# Agrobot_1_2.net
KiCad netlist of a schematic drawn in Altium Designer
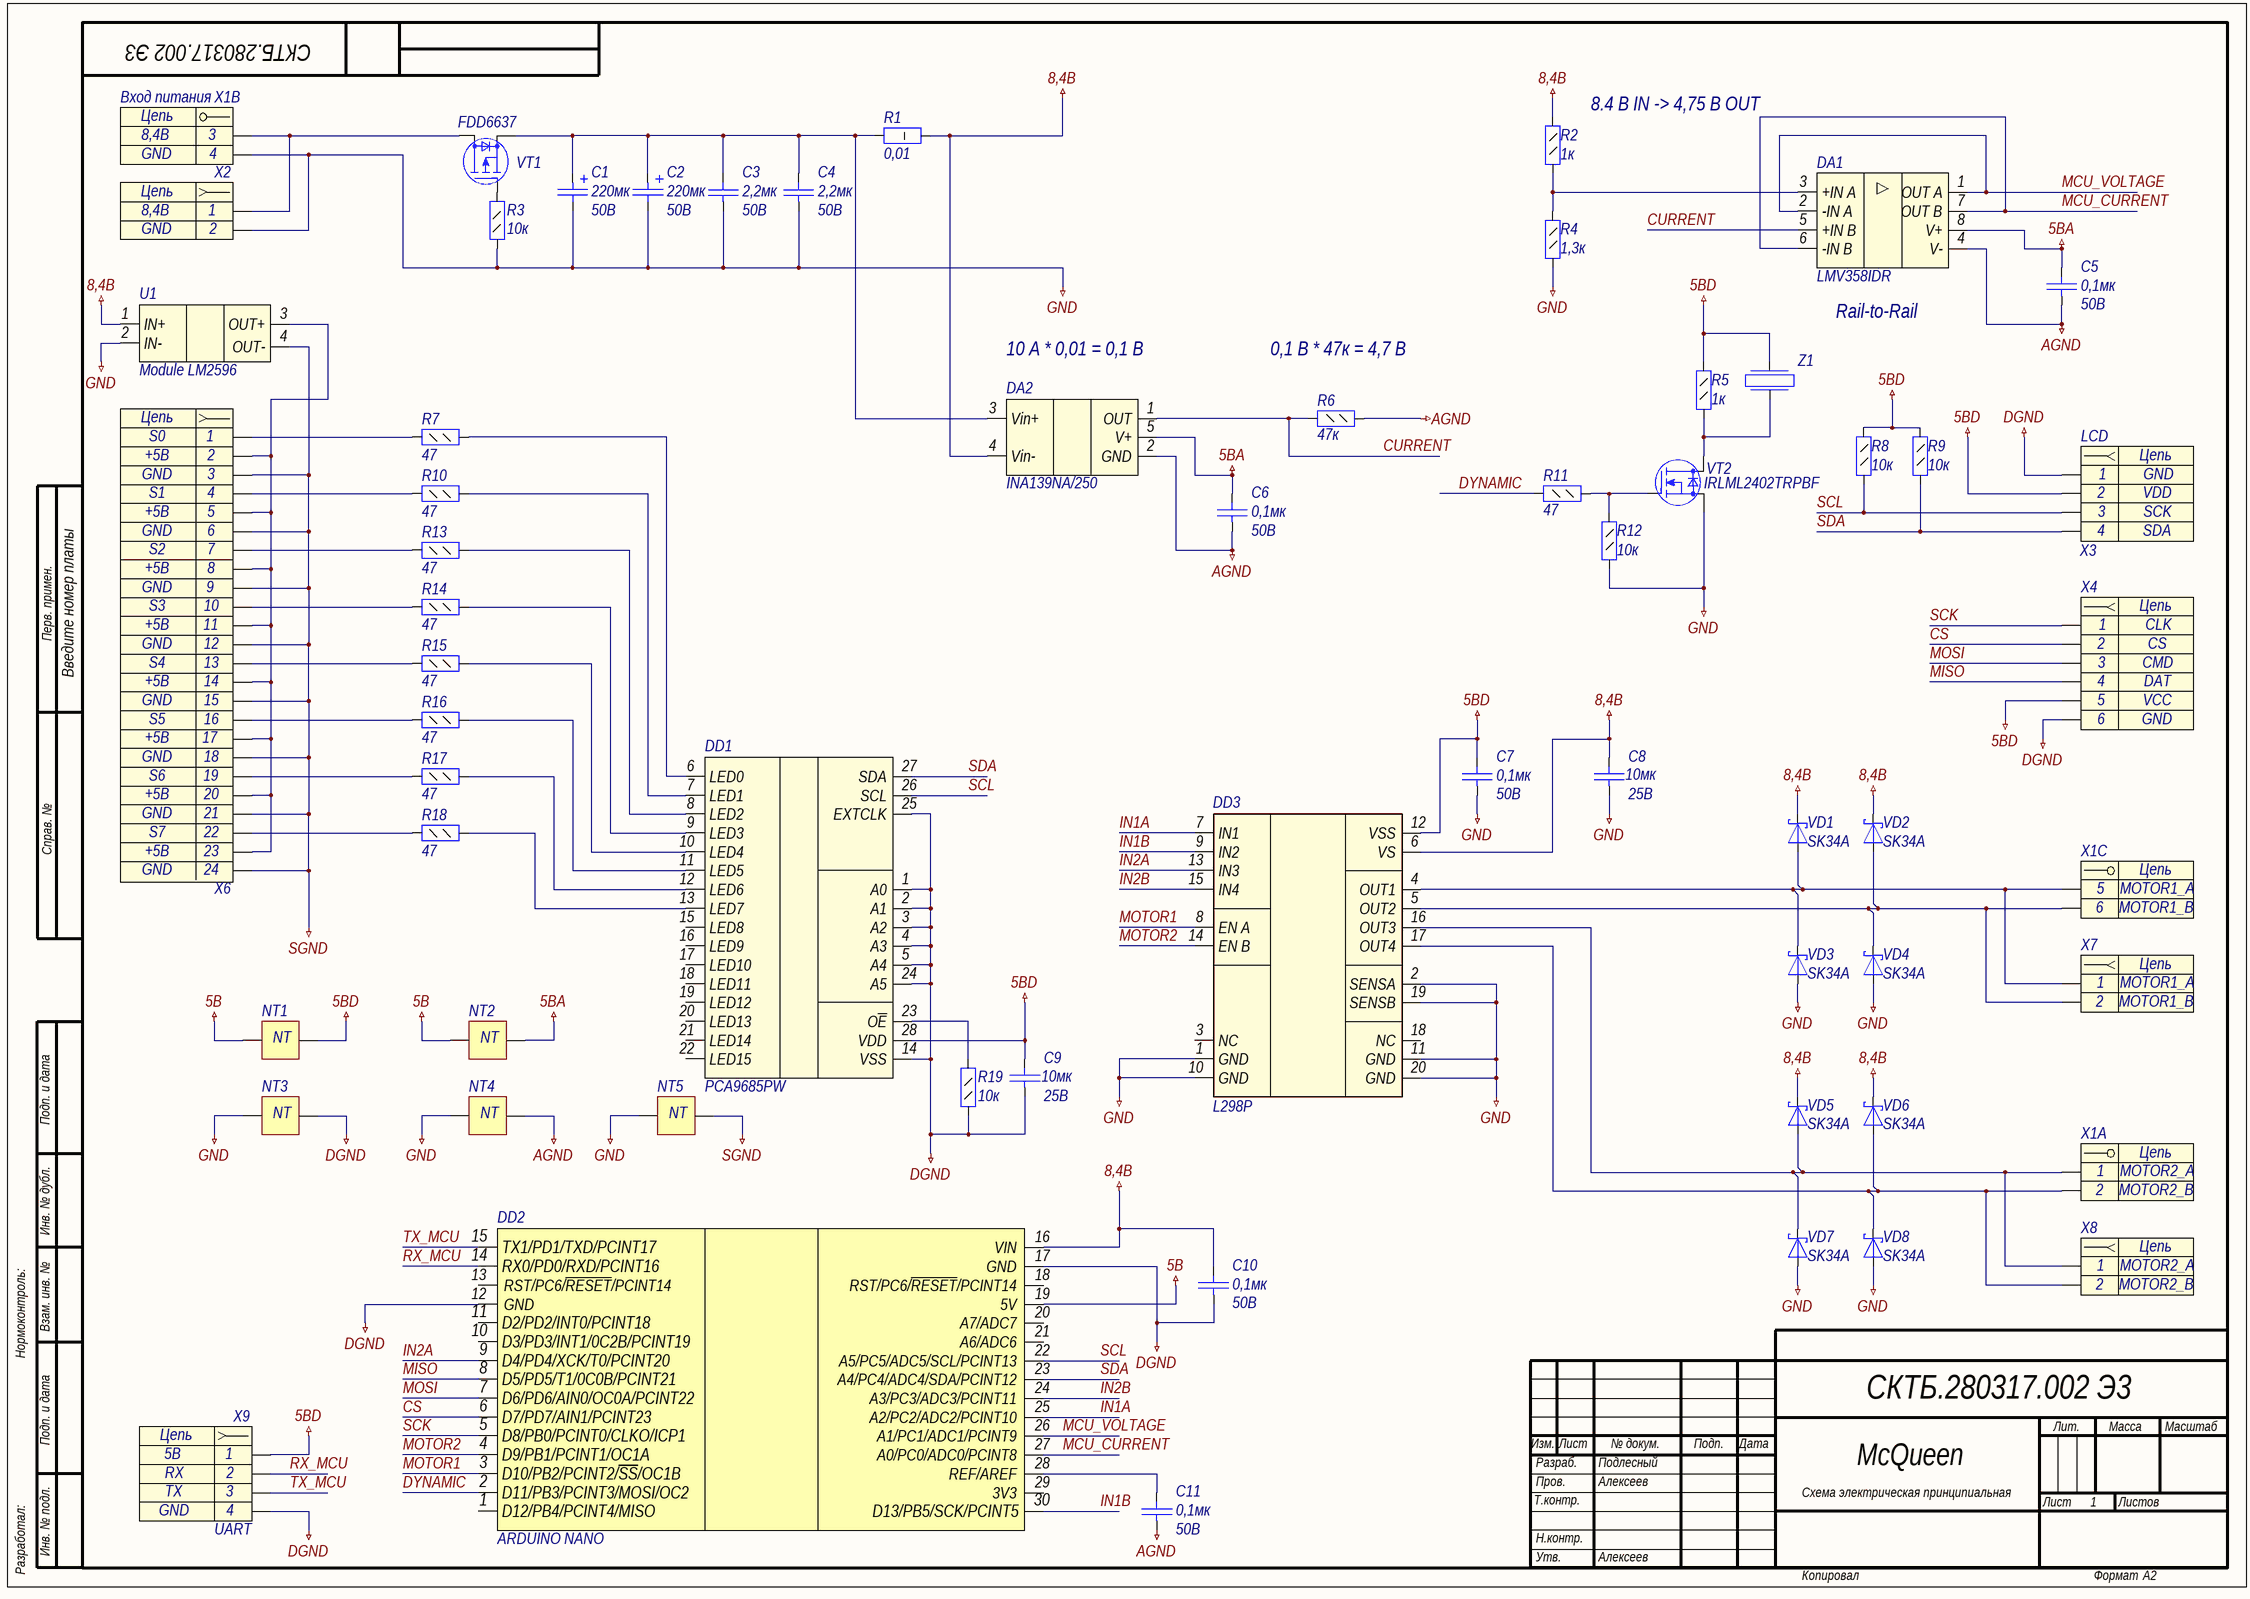
[diagram p0: Agrobot_1.2.SchDoc]

(export (version "E")
  (design (tool "Eeschema 10.0.6"))
  (components
    (comp (ref "C1")
      (value "220мк")
      (footprint "Cap_SMD_radial_polar(10x10.5)")
      (description "Конденсатор полярный")
      (fields
        (field (name "VOLTAGE") "50В")
        (field (name "PART NUMBER") "ECAP SMD")
        (field (name "Comment") "Capacitor_pol")
      )
      (libsource (lib "MOP44") (part "Capacitor_pol"))
    )
    (comp (ref "C2")
      (value "220мк")
      (footprint "Cap_SMD_radial_polar(10x10.5)")
      (description "Конденсатор полярный")
      (fields
        (field (name "VOLTAGE") "50В")
        (field (name "PART NUMBER") "ECAP SMD")
        (field (name "Comment") "Capacitor_pol")
      )
      (libsource (lib "MOP44") (part "Capacitor_pol"))
    )
    (comp (ref "C3")
      (value "2,2мк")
      (footprint "C1206")
      (description "Конденсатор")
      (fields
        (field (name "VOLTAGE") "50В")
        (field (name "PART NUMBER") "GRM31CR71H225KA88**L")
        (field (name "Comment") "Capacitor")
      )
      (libsource (lib "MOP44") (part "Capacitor"))
    )
    (comp (ref "C4")
      (value "2,2мк")
      (footprint "C1206")
      (description "Конденсатор")
      (fields
        (field (name "VOLTAGE") "50В")
        (field (name "PART NUMBER") "GRM31CR71H225KA88**L")
        (field (name "Comment") "Capacitor")
      )
      (libsource (lib "MOP44") (part "Capacitor"))
    )
    (comp (ref "C5")
      (value "0,1мк")
      (footprint "C0805")
      (description "Конденсатор")
      (fields
        (field (name "VOLTAGE") "50B")
        (field (name "PART NUMBER") "GRM21BR71E225K")
        (field (name "Comment") "Capacitor")
      )
      (libsource (lib "MOP44") (part "Capacitor"))
    )
    (comp (ref "C6")
      (value "0,1мк")
      (footprint "C0805")
      (description "Конденсатор")
      (fields
        (field (name "VOLTAGE") "50B")
        (field (name "PART NUMBER") "GRM21BR71E225K")
        (field (name "Comment") "Capacitor")
      )
      (libsource (lib "MOP44") (part "Capacitor"))
    )
    (comp (ref "C7")
      (value "0,1мк")
      (footprint "C0805")
      (description "Конденсатор")
      (fields
        (field (name "VOLTAGE") "50B")
        (field (name "PART NUMBER") "GRM21BR71E225K")
        (field (name "Comment") "Capacitor")
      )
      (libsource (lib "MOP44") (part "Capacitor"))
    )
    (comp (ref "C8")
      (value "10мк")
      (footprint "C1210")
      (description "Конденсатор")
      (fields
        (field (name "VOLTAGE") "25В")
        (field (name "PART NUMBER") "GRM32ER61A106K")
        (field (name "Comment") "Capacitor")
      )
      (libsource (lib "MOP44") (part "Capacitor"))
    )
    (comp (ref "C9")
      (value "10мк")
      (footprint "C1210")
      (description "Конденсатор")
      (fields
        (field (name "VOLTAGE") "25В")
        (field (name "PART NUMBER") "GRM32ER61A106K")
        (field (name "Comment") "Capacitor")
      )
      (libsource (lib "MOP44") (part "Capacitor"))
    )
    (comp (ref "C10")
      (value "0,1мк")
      (footprint "C0805")
      (description "Конденсатор")
      (fields
        (field (name "VOLTAGE") "50B")
        (field (name "PART NUMBER") "GRM21BR71E225K")
        (field (name "Comment") "Capacitor")
      )
      (libsource (lib "MOP44") (part "Capacitor"))
    )
    (comp (ref "C11")
      (value "0,1мк")
      (footprint "C0805")
      (description "Конденсатор")
      (fields
        (field (name "VOLTAGE") "50B")
        (field (name "PART NUMBER") "GRM21BR71E225K")
        (field (name "Comment") "Capacitor")
      )
      (libsource (lib "MOP44") (part "Capacitor"))
    )
    (comp (ref "DA1")
      (value "LMV358IDR")
      (footprint "SO8")
      (description "LOW-VOLTAGE RAIL-TO-RAIL OUTPUT OPERATIONAL AMPLIFIERS")
      (libsource (lib "MOP44") (part "LMV358IDR"))
    )
    (comp (ref "DA2")
      (value "INA139NA/250")
      (footprint "SOT23-5")
      (description "Измерительный датчик тока")
      (libsource (lib "MOP44") (part "INA139NA/250"))
    )
    (comp (ref "DD1")
      (value "PCA9685PW")
      (footprint "TSSOP28")
      (description "Драйвер светодиода, 16 выходов")
      (libsource (lib "MOP44") (part "PCA9685PW"))
    )
    (comp (ref "DD2")
      (value "ARDUINO NANO")
      (footprint "ARDUINO NANO")
      (description "Отладочная плата ATmega328")
      (libsource (lib "MOP44") (part "ARDUINO NANO"))
    )
    (comp (ref "DD3")
      (value "L298P")
      (footprint "POWERSO20")
      (description "FULL BRIDGE DC MOTOR DRIVER")
      (libsource (lib "MOP44") (part "L298P"))
    )
    (comp (ref "NT1")
      (value "Pofigistor")
      (footprint "Pofigistor0603")
      (libsource (lib "MOP44") (part "Pofigistor"))
    )
    (comp (ref "NT2")
      (value "Pofigistor")
      (footprint "Pofigistor0603")
      (libsource (lib "MOP44") (part "Pofigistor"))
    )
    (comp (ref "NT3")
      (value "Pofigistor")
      (footprint "Pofigistor0603")
      (libsource (lib "MOP44") (part "Pofigistor"))
    )
    (comp (ref "NT4")
      (value "Pofigistor")
      (footprint "Pofigistor0603")
      (libsource (lib "MOP44") (part "Pofigistor"))
    )
    (comp (ref "NT5")
      (value "Pofigistor")
      (footprint "Pofigistor0603")
      (libsource (lib "MOP44") (part "Pofigistor"))
    )
    (comp (ref "R1")
      (value "0,01")
      (footprint "R2512")
      (description "Резистор")
      (fields (field (name "POWER") "1Вт") (field (name "Comment") "Resistor_1Вт"))
      (libsource (lib "MOP44") (part "Resistor_1Вт"))
    )
    (comp (ref "R2")
      (value "1к")
      (footprint "R0805")
      (description "Резистор")
      (fields (field (name "POWER") "0,125Вт") (field (name "Comment") "Resistor_0,125Вт"))
      (libsource (lib "") (part "Resistor_0,125Вт_1"))
    )
    (comp (ref "R3")
      (value "10к")
      (footprint "R0805")
      (description "Резистор")
      (fields (field (name "PART NUMBER") "RC0805FR-0710KL") (field (name "POWER") "0,125Вт"))
      (libsource (lib "") (part "Resistor_0,125Вт_3"))
    )
    (comp (ref "R4")
      (value "1,3к")
      (footprint "R0805")
      (description "Резистор")
      (fields (field (name "POWER") "0,125Вт") (field (name "Comment") "Resistor_0,125Вт"))
      (libsource (lib "") (part "Resistor_0,125Вт_1"))
    )
    (comp (ref "R5")
      (value "1к")
      (footprint "R0805")
      (description "Резистор")
      (fields (field (name "POWER") "0,125Вт") (field (name "Comment") "Resistor_0,125Вт"))
      (libsource (lib "") (part "Resistor_0,125Вт_1"))
    )
    (comp (ref "R6")
      (value "47к")
      (footprint "R0805")
      (description "Резистор")
      (fields (field (name "POWER") "0,125Вт") (field (name "Comment") "Resistor_0,125Вт"))
      (libsource (lib "MOP44") (part "Resistor_0,125Вт"))
    )
    (comp (ref "R7")
      (value "47")
      (footprint "R0805")
      (description "Резистор")
      (fields (field (name "PART NUMBER") "RC0805FR-0747RL") (field (name "POWER") "0,125Вт"))
      (libsource (lib "") (part "Resistor_0,125Вт_2"))
    )
    (comp (ref "R8")
      (value "10к")
      (footprint "R0805")
      (description "Резистор")
      (fields (field (name "POWER") "0,125Вт") (field (name "Comment") "Resistor_0,125Вт"))
      (libsource (lib "") (part "Resistor_0,125Вт_1"))
    )
    (comp (ref "R9")
      (value "10к")
      (footprint "R0805")
      (description "Резистор")
      (fields (field (name "POWER") "0,125Вт") (field (name "Comment") "Resistor_0,125Вт"))
      (libsource (lib "") (part "Resistor_0,125Вт_1"))
    )
    (comp (ref "R10")
      (value "47")
      (footprint "R0805")
      (description "Резистор")
      (fields (field (name "PART NUMBER") "RC0805FR-0747RL") (field (name "POWER") "0,125Вт"))
      (libsource (lib "") (part "Resistor_0,125Вт_2"))
    )
    (comp (ref "R11")
      (value "47")
      (footprint "R0805")
      (description "Резистор")
      (fields (field (name "POWER") "0,125Вт") (field (name "Comment") "Resistor_0,125Вт"))
      (libsource (lib "MOP44") (part "Resistor_0,125Вт"))
    )
    (comp (ref "R12")
      (value "10к")
      (footprint "R0805")
      (description "Резистор")
      (fields (field (name "POWER") "0,125Вт") (field (name "Comment") "Resistor_0,125Вт"))
      (libsource (lib "") (part "Resistor_0,125Вт_1"))
    )
    (comp (ref "R13")
      (value "47")
      (footprint "R0805")
      (description "Резистор")
      (fields (field (name "PART NUMBER") "RC0805FR-0747RL") (field (name "POWER") "0,125Вт"))
      (libsource (lib "") (part "Resistor_0,125Вт_2"))
    )
    (comp (ref "R14")
      (value "47")
      (footprint "R0805")
      (description "Резистор")
      (fields (field (name "PART NUMBER") "RC0805FR-0747RL") (field (name "POWER") "0,125Вт"))
      (libsource (lib "") (part "Resistor_0,125Вт_2"))
    )
    (comp (ref "R15")
      (value "47")
      (footprint "R0805")
      (description "Резистор")
      (fields (field (name "PART NUMBER") "RC0805FR-0747RL") (field (name "POWER") "0,125Вт"))
      (libsource (lib "") (part "Resistor_0,125Вт_2"))
    )
    (comp (ref "R16")
      (value "47")
      (footprint "R0805")
      (description "Резистор")
      (fields (field (name "PART NUMBER") "RC0805FR-0747RL") (field (name "POWER") "0,125Вт"))
      (libsource (lib "") (part "Resistor_0,125Вт_2"))
    )
    (comp (ref "R17")
      (value "47")
      (footprint "R0805")
      (description "Резистор")
      (fields (field (name "PART NUMBER") "RC0805FR-0747RL") (field (name "POWER") "0,125Вт"))
      (libsource (lib "") (part "Resistor_0,125Вт_2"))
    )
    (comp (ref "R18")
      (value "47")
      (footprint "R0805")
      (description "Резистор")
      (fields (field (name "PART NUMBER") "RC0805FR-0747RL") (field (name "POWER") "0,125Вт"))
      (libsource (lib "") (part "Resistor_0,125Вт_2"))
    )
    (comp (ref "R19")
      (value "10к")
      (footprint "R0805")
      (description "Резистор")
      (fields (field (name "POWER") "0,125Вт") (field (name "Comment") "Resistor_0,125Вт"))
      (libsource (lib "") (part "Resistor_0,125Вт_3"))
    )
    (comp (ref "U1")
      (value "Module LM2596")
      (footprint "module LM2596")
      (description "Low-Dropout Regulator for 5-V to 3.3-V Conversion")
      (libsource (lib "MOP44") (part "Module LM2596"))
    )
    (comp (ref "VD1")
      (value "DiodeSchottky")
      (footprint "SMA")
      (description "Диод Шоттки")
      (fields (field (name "PART NUMBER") "SK34A"))
      (libsource (lib "MOP44") (part "DiodeSchottky"))
    )
    (comp (ref "VD2")
      (value "DiodeSchottky")
      (footprint "SMA")
      (description "Диод Шоттки")
      (fields (field (name "PART NUMBER") "SK34A"))
      (libsource (lib "MOP44") (part "DiodeSchottky"))
    )
    (comp (ref "VD3")
      (value "DiodeSchottky")
      (footprint "SMA")
      (description "Диод Шоттки")
      (fields (field (name "PART NUMBER") "SK34A"))
      (libsource (lib "MOP44") (part "DiodeSchottky"))
    )
    (comp (ref "VD4")
      (value "DiodeSchottky")
      (footprint "SMA")
      (description "Диод Шоттки")
      (fields (field (name "PART NUMBER") "SK34A"))
      (libsource (lib "MOP44") (part "DiodeSchottky"))
    )
    (comp (ref "VD5")
      (value "DiodeSchottky")
      (footprint "SMA")
      (description "Диод Шоттки")
      (fields (field (name "PART NUMBER") "SK34A"))
      (libsource (lib "MOP44") (part "DiodeSchottky"))
    )
    (comp (ref "VD6")
      (value "DiodeSchottky")
      (footprint "SMA")
      (description "Диод Шоттки")
      (fields (field (name "PART NUMBER") "SK34A"))
      (libsource (lib "MOP44") (part "DiodeSchottky"))
    )
    (comp (ref "VD7")
      (value "DiodeSchottky")
      (footprint "SMA")
      (description "Диод Шоттки")
      (fields (field (name "PART NUMBER") "SK34A"))
      (libsource (lib "MOP44") (part "DiodeSchottky"))
    )
    (comp (ref "VD8")
      (value "DiodeSchottky")
      (footprint "SMA")
      (description "Диод Шоттки")
      (fields (field (name "PART NUMBER") "SK34A"))
      (libsource (lib "MOP44") (part "DiodeSchottky"))
    )
    (comp (ref "VT1")
      (value "P-MOSFET")
      (footprint "D2PAK")
      (description "N-MOSFET")
      (fields (field (name "PART NUMBER") "FDD6637") (field (name "MANUFACTURER") "Fairchild Semiconductor"))
      (libsource (lib "MOP44") (part "P-MOSFET"))
    )
    (comp (ref "VT2")
      (value "N-MOSFET")
      (footprint "SOT23-3")
      (fields (field (name "PART NUMBER") "IRLML2402TRPBF"))
      (libsource (lib "MOP44") (part "N-MOSFET"))
    )
    (comp (ref "X1")
      (value "Вход питания")
      (footprint "TERMINAL-6WAY-5MM")
      (description "POWER")
      (libsource (lib "MOP44") (part "Header_6_motor"))
    )
    (comp (ref "X2")
      (value "Header_2_sct")
      (footprint "2HOLE_2.5")
      (description "Разъем - 2 конт. розетка")
      (libsource (lib "MOP44") (part "Header_2_sct"))
    )
    (comp (ref "X3")
      (value "LCD")
      (footprint "PLS-4HOLES")
      (description "Разъем - 4 конт. розетка")
      (libsource (lib "MOP44") (part "Header_4_sct"))
    )
    (comp (ref "X4")
      (value "Header_6_sct")
      (footprint "PSP_ANTENNA")
      (description "Разъем - 6 конт. розетка")
      (libsource (lib "MOP44") (part "Header_6_sct"))
    )
    (comp (ref "X6")
      (value "Header_24_sct")
      (footprint "PLS-24-3")
      (description "Разъем - 5 конт. розетка")
      (libsource (lib "MOP44") (part "Header_24_sct"))
    )
    (comp (ref "X7")
      (value "Header_2_sct")
      (footprint "2HOLE_2.5")
      (description "Разъем - 2 конт. розетка")
      (libsource (lib "") (part "Header_2_sct_1"))
    )
    (comp (ref "X8")
      (value "Header_2_sct")
      (footprint "2HOLE_2.5")
      (description "Разъем - 2 конт. розетка")
      (libsource (lib "") (part "Header_2_sct_1"))
    )
    (comp (ref "X9")
      (value "UART")
      (footprint "PLS-4HOLES")
      (description "Разъем - 4 конт. розетка")
      (libsource (lib "") (part "Header_4_sct_1"))
    )
    (comp (ref "Z1")
      (value "~")
      (footprint "Buzzer_9mm")
      (description "Пьезоизлучатель звуковой без генератора")
      (fields (field (name "PART NUMBER") "HC0905F"))
      (libsource (lib "MOP44") (part "Buzzer"))
    )
  )
  (nets
    (net (code "1") (name "/CS") (class "Default")
      (node (ref "DD2") (pin "6") (pinfunction "D7/PD7/AIN1/PCINT23_6") (pintype "passive"))
      (node (ref "X4") (pin "2") (pinfunction "2_2") (pintype "passive"))
    )
    (net (code "2") (name "/CURRENT") (class "Default")
      (node (ref "DA1") (pin "5") (pinfunction "+IN_B_5") (pintype "passive"))
      (node (ref "DA2") (pin "1") (pinfunction "OUT_1") (pintype "power_in"))
      (node (ref "R6") (pin "2") (pinfunction "2_2") (pintype "passive"))
    )
    (net (code "3") (name "/DYNAMIC") (class "Default")
      (node (ref "DD2") (pin "2") (pinfunction "D11/PB3/PCINT3/MOSI/OC2_2") (pintype "passive"))
      (node (ref "R11") (pin "2") (pinfunction "2_2") (pintype "passive"))
    )
    (net (code "4") (name "/IN1A") (class "Default")
      (node (ref "DD2") (pin "25") (pinfunction "A2/PC2/ADC2/PCINT10_25") (pintype "passive"))
      (node (ref "DD3") (pin "7") (pinfunction "IN1_7") (pintype "passive"))
    )
    (net (code "5") (name "/IN1B") (class "Default")
      (node (ref "DD2") (pin "30") (pinfunction "D13/PB5/SCK/PCINT5_30") (pintype "passive"))
      (node (ref "DD3") (pin "9") (pinfunction "IN2_9") (pintype "passive"))
    )
    (net (code "6") (name "/IN2A") (class "Default")
      (node (ref "DD2") (pin "9") (pinfunction "D4/PD4/XCK/T0/PCINT20_9") (pintype "passive"))
      (node (ref "DD3") (pin "13") (pinfunction "IN3_13") (pintype "passive"))
    )
    (net (code "7") (name "/IN2B") (class "Default")
      (node (ref "DD2") (pin "24") (pinfunction "A3/PC3/ADC3/PCINT11_24") (pintype "passive"))
      (node (ref "DD3") (pin "15") (pinfunction "IN4_15") (pintype "passive"))
    )
    (net (code "8") (name "/MCU_CURRENT") (class "Default")
      (node (ref "DA1") (pin "6") (pinfunction "-IN_B_6") (pintype "passive"))
      (node (ref "DA1") (pin "7") (pinfunction "OUT_B_7") (pintype "passive"))
      (node (ref "DD2") (pin "27") (pinfunction "A0/PC0/ADC0/PCINT8_27") (pintype "passive"))
    )
    (net (code "9") (name "/MCU_VOLTAGE") (class "Default")
      (node (ref "DA1") (pin "1") (pinfunction "OUT_A_1") (pintype "passive"))
      (node (ref "DA1") (pin "2") (pinfunction "-IN_A_2") (pintype "passive"))
      (node (ref "DD2") (pin "26") (pinfunction "A1/PC1/ADC1/PCINT9_26") (pintype "passive"))
    )
    (net (code "10") (name "/MISO") (class "Default")
      (node (ref "DD2") (pin "8") (pinfunction "D5/PD5/T1/0C0B/PCINT21_8") (pintype "passive"))
      (node (ref "X4") (pin "4") (pinfunction "4_4") (pintype "passive"))
    )
    (net (code "11") (name "/MOSI") (class "Default")
      (node (ref "DD2") (pin "7") (pinfunction "D6/PD6/AIN0/OC0A/PCINT22_7") (pintype "passive"))
      (node (ref "X4") (pin "3") (pinfunction "3_3") (pintype "passive"))
    )
    (net (code "12") (name "/MOTOR1") (class "Default")
      (node (ref "DD2") (pin "3") (pinfunction "D10/PB2/PCINT2/~{SS}/OC1B_3") (pintype "passive"))
      (node (ref "DD3") (pin "8") (pinfunction "EN_A_8") (pintype "passive"))
    )
    (net (code "13") (name "/MOTOR2") (class "Default")
      (node (ref "DD2") (pin "4") (pinfunction "D9/PB1/PCINT1/OC1A_4") (pintype "passive"))
      (node (ref "DD3") (pin "14") (pinfunction "EN_B_14") (pintype "passive"))
    )
    (net (code "14") (name "/RX_MCU") (class "Default")
      (node (ref "DD2") (pin "14") (pinfunction "RX0/PD0/RXD/PCINT16_14") (pintype "passive"))
      (node (ref "X9") (pin "2") (pinfunction "2_2") (pintype "passive"))
    )
    (net (code "15") (name "/SCK") (class "Default")
      (node (ref "DD2") (pin "5") (pinfunction "D8/PB0/PCINT0/CLKO/ICP1_5") (pintype "passive"))
      (node (ref "X4") (pin "1") (pinfunction "1_1") (pintype "passive"))
    )
    (net (code "16") (name "/SCL") (class "Default")
      (node (ref "DD1") (pin "26") (pinfunction "SCL_26") (pintype "power_in"))
      (node (ref "DD2") (pin "22") (pinfunction "A5/PC5/ADC5/SCL/PCINT13_22") (pintype "passive"))
      (node (ref "R8") (pin "2") (pinfunction "2_2") (pintype "passive"))
      (node (ref "X3") (pin "3") (pinfunction "3_3") (pintype "passive"))
    )
    (net (code "17") (name "/SDA") (class "Default")
      (node (ref "DD1") (pin "27") (pinfunction "SDA_27") (pintype "power_in"))
      (node (ref "DD2") (pin "23") (pinfunction "A4/PC4/ADC4/SDA/PCINT12_23") (pintype "passive"))
      (node (ref "R9") (pin "2") (pinfunction "2_2") (pintype "passive"))
      (node (ref "X3") (pin "4") (pinfunction "4_4") (pintype "passive"))
    )
    (net (code "18") (name "/TX_MCU") (class "Default")
      (node (ref "DD2") (pin "15") (pinfunction "TX1/PD1/TXD/PCINT17_15") (pintype "passive"))
      (node (ref "X9") (pin "3") (pinfunction "3_3") (pintype "passive"))
    )
    (net (code "19") (name "5В") (class "Default")
      (node (ref "DD2") (pin "19") (pinfunction "5V_19") (pintype "passive"))
      (node (ref "NT1") (pin "1") (pinfunction "1_1") (pintype "passive"))
      (node (ref "NT2") (pin "1") (pinfunction "1_1") (pintype "passive"))
    )
    (net (code "20") (name "5ВA") (class "Default")
      (node (ref "C5") (pin "2") (pinfunction "2_2") (pintype "passive"))
      (node (ref "C6") (pin "2") (pinfunction "2_2") (pintype "passive"))
      (node (ref "DA1") (pin "8") (pinfunction "V+_8") (pintype "passive"))
      (node (ref "DA2") (pin "5") (pinfunction "V+_5") (pintype "power_in"))
      (node (ref "NT2") (pin "2") (pinfunction "2_2") (pintype "passive"))
    )
    (net (code "21") (name "5ВD") (class "Default")
      (node (ref "C7") (pin "2") (pinfunction "2_2") (pintype "passive"))
      (node (ref "C9") (pin "2") (pinfunction "2_2") (pintype "passive"))
      (node (ref "DD1") (pin "28") (pinfunction "VDD_28") (pintype "power_in"))
      (node (ref "DD3") (pin "12") (pinfunction "VSS_12") (pintype "passive"))
      (node (ref "NT1") (pin "2") (pinfunction "2_2") (pintype "passive"))
      (node (ref "R5") (pin "1") (pinfunction "1_1") (pintype "passive"))
      (node (ref "R8") (pin "1") (pinfunction "1_1") (pintype "passive"))
      (node (ref "R9") (pin "1") (pinfunction "1_1") (pintype "passive"))
      (node (ref "X3") (pin "2") (pinfunction "2_2") (pintype "passive"))
      (node (ref "X4") (pin "5") (pinfunction "5_5") (pintype "passive"))
      (node (ref "X9") (pin "1") (pinfunction "1_1") (pintype "passive"))
      (node (ref "Z1") (pin "2") (pinfunction "2_2") (pintype "passive"))
    )
    (net (code "22") (name "8,4В") (class "Default")
      (node (ref "C10") (pin "2") (pinfunction "2_2") (pintype "passive"))
      (node (ref "C8") (pin "2") (pinfunction "2_2") (pintype "passive"))
      (node (ref "DA2") (pin "4") (pinfunction "Vin-_4") (pintype "power_in"))
      (node (ref "DD2") (pin "16") (pinfunction "VIN_16") (pintype "passive"))
      (node (ref "DD3") (pin "6") (pinfunction "VS_6") (pintype "passive"))
      (node (ref "R1") (pin "2") (pinfunction "5_2") (pintype "passive"))
      (node (ref "R2") (pin "1") (pinfunction "1_1") (pintype "passive"))
      (node (ref "U1") (pin "1") (pinfunction "IN+_1") (pintype "power_in"))
      (node (ref "VD1") (pin "1") (pinfunction "K_1") (pintype "passive"))
      (node (ref "VD2") (pin "1") (pinfunction "K_1") (pintype "passive"))
      (node (ref "VD5") (pin "1") (pinfunction "K_1") (pintype "passive"))
      (node (ref "VD6") (pin "1") (pinfunction "K_1") (pintype "passive"))
    )
    (net (code "23") (name "AGND") (class "Default")
      (node (ref "C11") (pin "1") (pinfunction "1_1") (pintype "passive"))
      (node (ref "C5") (pin "1") (pinfunction "1_1") (pintype "passive"))
      (node (ref "C6") (pin "1") (pinfunction "1_1") (pintype "passive"))
      (node (ref "DA1") (pin "4") (pinfunction "V-_4") (pintype "passive"))
      (node (ref "DA2") (pin "2") (pinfunction "GND_2") (pintype "power_in"))
      (node (ref "NT4") (pin "2") (pinfunction "2_2") (pintype "passive"))
      (node (ref "R6") (pin "1") (pinfunction "1_1") (pintype "passive"))
    )
    (net (code "24") (name "DGND") (class "Default")
      (node (ref "C10") (pin "1") (pinfunction "1_1") (pintype "passive"))
      (node (ref "C9") (pin "1") (pinfunction "1_1") (pintype "passive"))
      (node (ref "DD1") (pin "1") (pinfunction "A0_1") (pintype "power_in"))
      (node (ref "DD1") (pin "14") (pinfunction "VSS_14") (pintype "power_in"))
      (node (ref "DD1") (pin "2") (pinfunction "A1_2") (pintype "power_in"))
      (node (ref "DD1") (pin "24") (pinfunction "A5_24") (pintype "power_in"))
      (node (ref "DD1") (pin "25") (pinfunction "EXTCLK_25") (pintype "power_in"))
      (node (ref "DD1") (pin "3") (pinfunction "A2_3") (pintype "power_in"))
      (node (ref "DD1") (pin "4") (pinfunction "A3_4") (pintype "power_in"))
      (node (ref "DD1") (pin "5") (pinfunction "A4_5") (pintype "power_in"))
      (node (ref "DD2") (pin "12") (pinfunction "GND_12") (pintype "passive"))
      (node (ref "DD2") (pin "17") (pinfunction "GND_17") (pintype "passive"))
      (node (ref "NT3") (pin "2") (pinfunction "2_2") (pintype "passive"))
      (node (ref "R19") (pin "1") (pinfunction "1_1") (pintype "passive"))
      (node (ref "X3") (pin "1") (pinfunction "1_1") (pintype "passive"))
      (node (ref "X4") (pin "6") (pinfunction "6_6") (pintype "passive"))
      (node (ref "X9") (pin "4") (pinfunction "4_4") (pintype "passive"))
    )
    (net (code "25") (name "GND") (class "Default")
      (node (ref "C1") (pin "2") (pinfunction "2_2") (pintype "passive"))
      (node (ref "C2") (pin "2") (pinfunction "2_2") (pintype "passive"))
      (node (ref "C3") (pin "1") (pinfunction "1_1") (pintype "passive"))
      (node (ref "C4") (pin "1") (pinfunction "1_1") (pintype "passive"))
      (node (ref "C7") (pin "1") (pinfunction "1_1") (pintype "passive"))
      (node (ref "C8") (pin "1") (pinfunction "1_1") (pintype "passive"))
      (node (ref "DD3") (pin "1") (pinfunction "GND_1") (pintype "passive"))
      (node (ref "DD3") (pin "10") (pinfunction "GND_10") (pintype "passive"))
      (node (ref "DD3") (pin "11") (pinfunction "GND_11") (pintype "passive"))
      (node (ref "DD3") (pin "19") (pinfunction "SENSB_19") (pintype "passive"))
      (node (ref "DD3") (pin "2") (pinfunction "SENSA_2") (pintype "passive"))
      (node (ref "DD3") (pin "20") (pinfunction "GND_20") (pintype "passive"))
      (node (ref "NT3") (pin "1") (pinfunction "1_1") (pintype "passive"))
      (node (ref "NT4") (pin "1") (pinfunction "1_1") (pintype "passive"))
      (node (ref "NT5") (pin "1") (pinfunction "1_1") (pintype "passive"))
      (node (ref "R12") (pin "2") (pinfunction "2_2") (pintype "passive"))
      (node (ref "R3") (pin "1") (pinfunction "1_1") (pintype "passive"))
      (node (ref "R4") (pin "2") (pinfunction "2_2") (pintype "passive"))
      (node (ref "U1") (pin "2") (pinfunction "IN-_2") (pintype "power_in"))
      (node (ref "VD3") (pin "2") (pinfunction "A_2") (pintype "passive"))
      (node (ref "VD4") (pin "2") (pinfunction "A_2") (pintype "passive"))
      (node (ref "VD7") (pin "2") (pinfunction "A_2") (pintype "passive"))
      (node (ref "VD8") (pin "2") (pinfunction "A_2") (pintype "passive"))
      (node (ref "VT2") (pin "2") (pinfunction "S_2") (pintype "passive"))
      (node (ref "X1") (pin "4") (pinfunction "4_4") (pintype "passive"))
      (node (ref "X2") (pin "2") (pinfunction "2_2") (pintype "passive"))
    )
    (net (code "26") (name "Net-(DA1-+IN_A)") (class "Default")
      (node (ref "DA1") (pin "3") (pinfunction "+IN_A_3") (pintype "passive"))
      (node (ref "R2") (pin "2") (pinfunction "2_2") (pintype "passive"))
      (node (ref "R4") (pin "1") (pinfunction "1_1") (pintype "passive"))
    )
    (net (code "27") (name "Net-(DA2-Vin+)") (class "Default")
      (node (ref "C1") (pin "1") (pinfunction "1_1") (pintype "passive"))
      (node (ref "C2") (pin "1") (pinfunction "1_1") (pintype "passive"))
      (node (ref "C3") (pin "2") (pinfunction "2_2") (pintype "passive"))
      (node (ref "C4") (pin "2") (pinfunction "2_2") (pintype "passive"))
      (node (ref "DA2") (pin "3") (pinfunction "Vin+_3") (pintype "power_in"))
      (node (ref "R1") (pin "1") (pinfunction "1_1") (pintype "passive"))
      (node (ref "VT1") (pin "2") (pinfunction "S_2") (pintype "passive"))
    )
    (net (code "28") (name "Net-(DD1-LED0)") (class "Default")
      (node (ref "DD1") (pin "6") (pinfunction "LED0_6") (pintype "power_in"))
      (node (ref "R7") (pin "2") (pinfunction "2_2") (pintype "passive"))
    )
    (net (code "29") (name "Net-(DD1-LED1)") (class "Default")
      (node (ref "DD1") (pin "7") (pinfunction "LED1_7") (pintype "power_in"))
      (node (ref "R10") (pin "2") (pinfunction "2_2") (pintype "passive"))
    )
    (net (code "30") (name "Net-(DD1-LED2)") (class "Default")
      (node (ref "DD1") (pin "8") (pinfunction "LED2_8") (pintype "power_in"))
      (node (ref "R13") (pin "2") (pinfunction "2_2") (pintype "passive"))
    )
    (net (code "31") (name "Net-(DD1-LED3)") (class "Default")
      (node (ref "DD1") (pin "9") (pinfunction "LED3_9") (pintype "power_in"))
      (node (ref "R14") (pin "2") (pinfunction "2_2") (pintype "passive"))
    )
    (net (code "32") (name "Net-(DD1-LED4)") (class "Default")
      (node (ref "DD1") (pin "10") (pinfunction "LED4_10") (pintype "power_in"))
      (node (ref "R15") (pin "2") (pinfunction "2_2") (pintype "passive"))
    )
    (net (code "33") (name "Net-(DD1-LED5)") (class "Default")
      (node (ref "DD1") (pin "11") (pinfunction "LED5_11") (pintype "power_in"))
      (node (ref "R16") (pin "2") (pinfunction "2_2") (pintype "passive"))
    )
    (net (code "34") (name "Net-(DD1-LED6)") (class "Default")
      (node (ref "DD1") (pin "12") (pinfunction "LED6_12") (pintype "power_in"))
      (node (ref "R17") (pin "2") (pinfunction "2_2") (pintype "passive"))
    )
    (net (code "35") (name "Net-(DD1-LED7)") (class "Default")
      (node (ref "DD1") (pin "13") (pinfunction "LED7_13") (pintype "power_in"))
      (node (ref "R18") (pin "2") (pinfunction "2_2") (pintype "passive"))
    )
    (net (code "36") (name "Net-(DD1-O~{E})") (class "Default")
      (node (ref "DD1") (pin "23") (pinfunction "O~{E}_23") (pintype "power_in"))
      (node (ref "R19") (pin "2") (pinfunction "2_2") (pintype "passive"))
    )
    (net (code "37") (name "Net-(DD2-REF{slash}AREF)") (class "Default")
      (node (ref "C11") (pin "2") (pinfunction "2_2") (pintype "passive"))
      (node (ref "DD2") (pin "28") (pinfunction "REF/AREF_28") (pintype "passive"))
    )
    (net (code "38") (name "Net-(DD3-OUT1)") (class "Default")
      (node (ref "DD3") (pin "4") (pinfunction "OUT1_4") (pintype "passive"))
      (node (ref "VD1") (pin "2") (pinfunction "A_2") (pintype "passive"))
      (node (ref "VD3") (pin "1") (pinfunction "K_1") (pintype "passive"))
      (node (ref "X1") (pin "5") (pinfunction "5_5") (pintype "passive"))
      (node (ref "X7") (pin "1") (pinfunction "1_1") (pintype "passive"))
    )
    (net (code "39") (name "Net-(DD3-OUT2)") (class "Default")
      (node (ref "DD3") (pin "5") (pinfunction "OUT2_5") (pintype "passive"))
      (node (ref "VD2") (pin "2") (pinfunction "A_2") (pintype "passive"))
      (node (ref "VD4") (pin "1") (pinfunction "K_1") (pintype "passive"))
      (node (ref "X1") (pin "6") (pinfunction "6_6") (pintype "passive"))
      (node (ref "X7") (pin "2") (pinfunction "2_2") (pintype "passive"))
    )
    (net (code "40") (name "Net-(DD3-OUT3)") (class "Default")
      (node (ref "DD3") (pin "16") (pinfunction "OUT3_16") (pintype "passive"))
      (node (ref "VD5") (pin "2") (pinfunction "A_2") (pintype "passive"))
      (node (ref "VD7") (pin "1") (pinfunction "K_1") (pintype "passive"))
      (node (ref "X1") (pin "1") (pinfunction "1_1") (pintype "passive"))
      (node (ref "X8") (pin "1") (pinfunction "1_1") (pintype "passive"))
    )
    (net (code "41") (name "Net-(DD3-OUT4)") (class "Default")
      (node (ref "DD3") (pin "17") (pinfunction "OUT4_17") (pintype "passive"))
      (node (ref "VD6") (pin "2") (pinfunction "A_2") (pintype "passive"))
      (node (ref "VD8") (pin "1") (pinfunction "K_1") (pintype "passive"))
      (node (ref "X1") (pin "2") (pinfunction "2_2") (pintype "passive"))
      (node (ref "X8") (pin "2") (pinfunction "2_2") (pintype "passive"))
    )
    (net (code "42") (name "Net-(R7-Pad1)") (class "Default")
      (node (ref "R7") (pin "1") (pinfunction "1_1") (pintype "passive"))
      (node (ref "X6") (pin "1") (pinfunction "1_1") (pintype "passive"))
    )
    (net (code "43") (name "Net-(R10-Pad1)") (class "Default")
      (node (ref "R10") (pin "1") (pinfunction "1_1") (pintype "passive"))
      (node (ref "X6") (pin "4") (pinfunction "4_4") (pintype "passive"))
    )
    (net (code "44") (name "Net-(R13-Pad1)") (class "Default")
      (node (ref "R13") (pin "1") (pinfunction "1_1") (pintype "passive"))
      (node (ref "X6") (pin "7") (pinfunction "7_7") (pintype "passive"))
    )
    (net (code "45") (name "Net-(R14-Pad1)") (class "Default")
      (node (ref "R14") (pin "1") (pinfunction "1_1") (pintype "passive"))
      (node (ref "X6") (pin "10") (pinfunction "10_10") (pintype "passive"))
    )
    (net (code "46") (name "Net-(R15-Pad1)") (class "Default")
      (node (ref "R15") (pin "1") (pinfunction "1_1") (pintype "passive"))
      (node (ref "X6") (pin "13") (pinfunction "13_13") (pintype "passive"))
    )
    (net (code "47") (name "Net-(R16-Pad1)") (class "Default")
      (node (ref "R16") (pin "1") (pinfunction "1_1") (pintype "passive"))
      (node (ref "X6") (pin "16") (pinfunction "16_16") (pintype "passive"))
    )
    (net (code "48") (name "Net-(R17-Pad1)") (class "Default")
      (node (ref "R17") (pin "1") (pinfunction "1_1") (pintype "passive"))
      (node (ref "X6") (pin "19") (pinfunction "19_19") (pintype "passive"))
    )
    (net (code "49") (name "Net-(R18-Pad1)") (class "Default")
      (node (ref "R18") (pin "1") (pinfunction "1_1") (pintype "passive"))
      (node (ref "X6") (pin "22") (pinfunction "22_22") (pintype "passive"))
    )
    (net (code "50") (name "Net-(U1-OUT+)") (class "Default")
      (node (ref "U1") (pin "3") (pinfunction "OUT+_3") (pintype "power_in"))
      (node (ref "X6") (pin "11") (pinfunction "11_11") (pintype "passive"))
      (node (ref "X6") (pin "14") (pinfunction "14_14") (pintype "passive"))
      (node (ref "X6") (pin "17") (pinfunction "17_17") (pintype "passive"))
      (node (ref "X6") (pin "2") (pinfunction "2_2") (pintype "passive"))
      (node (ref "X6") (pin "20") (pinfunction "20_20") (pintype "passive"))
      (node (ref "X6") (pin "23") (pinfunction "23_23") (pintype "passive"))
      (node (ref "X6") (pin "5") (pinfunction "5_5") (pintype "passive"))
      (node (ref "X6") (pin "8") (pinfunction "8_8") (pintype "passive"))
    )
    (net (code "51") (name "Net-(VT1-D)") (class "Default")
      (node (ref "VT1") (pin "3") (pinfunction "D_3") (pintype "passive"))
      (node (ref "X1") (pin "3") (pinfunction "3_3") (pintype "passive"))
      (node (ref "X2") (pin "1") (pinfunction "1_1") (pintype "passive"))
    )
    (net (code "52") (name "Net-(VT1-G)") (class "Default")
      (node (ref "R3") (pin "2") (pinfunction "2_2") (pintype "passive"))
      (node (ref "VT1") (pin "1") (pinfunction "G_1") (pintype "passive"))
    )
    (net (code "53") (name "Net-(VT2-D)") (class "Default")
      (node (ref "R5") (pin "2") (pinfunction "2_2") (pintype "passive"))
      (node (ref "VT2") (pin "3") (pinfunction "D_3") (pintype "passive"))
      (node (ref "Z1") (pin "1") (pinfunction "1_1") (pintype "passive"))
    )
    (net (code "54") (name "Net-(VT2-G)") (class "Default")
      (node (ref "R11") (pin "1") (pinfunction "1_1") (pintype "passive"))
      (node (ref "R12") (pin "1") (pinfunction "1_1") (pintype "passive"))
      (node (ref "VT2") (pin "1") (pinfunction "G_1") (pintype "passive"))
    )
    (net (code "55") (name "SGND") (class "Default")
      (node (ref "NT5") (pin "2") (pinfunction "2_2") (pintype "passive"))
      (node (ref "U1") (pin "4") (pinfunction "OUT-_4") (pintype "power_in"))
      (node (ref "X6") (pin "12") (pinfunction "12_12") (pintype "passive"))
      (node (ref "X6") (pin "15") (pinfunction "15_15") (pintype "passive"))
      (node (ref "X6") (pin "18") (pinfunction "18_18") (pintype "passive"))
      (node (ref "X6") (pin "21") (pinfunction "21_21") (pintype "passive"))
      (node (ref "X6") (pin "24") (pinfunction "24_24") (pintype "passive"))
      (node (ref "X6") (pin "3") (pinfunction "3_3") (pintype "passive"))
      (node (ref "X6") (pin "6") (pinfunction "6_6") (pintype "passive"))
      (node (ref "X6") (pin "9") (pinfunction "9_9") (pintype "passive"))
    )
    (net (code "56") (name "unconnected-(DD1-LED8-Pad15)") (class "Default")
      (node (ref "DD1") (pin "15") (pinfunction "LED8_15") (pintype "power_in"))
    )
    (net (code "57") (name "unconnected-(DD1-LED9-Pad16)") (class "Default")
      (node (ref "DD1") (pin "16") (pinfunction "LED9_16") (pintype "power_in"))
    )
    (net (code "58") (name "unconnected-(DD1-LED10-Pad17)") (class "Default")
      (node (ref "DD1") (pin "17") (pinfunction "LED10_17") (pintype "power_in"))
    )
    (net (code "59") (name "unconnected-(DD1-LED11-Pad18)") (class "Default")
      (node (ref "DD1") (pin "18") (pinfunction "LED11_18") (pintype "power_in"))
    )
    (net (code "60") (name "unconnected-(DD1-LED12-Pad19)") (class "Default")
      (node (ref "DD1") (pin "19") (pinfunction "LED12_19") (pintype "power_in"))
    )
    (net (code "61") (name "unconnected-(DD1-LED13-Pad20)") (class "Default")
      (node (ref "DD1") (pin "20") (pinfunction "LED13_20") (pintype "power_in"))
    )
    (net (code "62") (name "unconnected-(DD1-LED14-Pad21)") (class "Default")
      (node (ref "DD1") (pin "21") (pinfunction "LED14_21") (pintype "power_in"))
    )
    (net (code "63") (name "unconnected-(DD1-LED15-Pad22)") (class "Default")
      (node (ref "DD1") (pin "22") (pinfunction "LED15_22") (pintype "power_in"))
    )
    (net (code "64") (name "unconnected-(DD2-3V3-Pad29)") (class "Default")
      (node (ref "DD2") (pin "29") (pinfunction "3V3_29") (pintype "passive"))
    )
    (net (code "65") (name "unconnected-(DD2-A6{slash}ADC6-Pad21)") (class "Default")
      (node (ref "DD2") (pin "21") (pinfunction "A6/ADC6_21") (pintype "passive"))
    )
    (net (code "66") (name "unconnected-(DD2-A7{slash}ADC7-Pad20)") (class "Default")
      (node (ref "DD2") (pin "20") (pinfunction "A7/ADC7_20") (pintype "passive"))
    )
    (net (code "67") (name "unconnected-(DD2-D2{slash}PD2{slash}INT0{slash}PCINT18-Pad11)") (class "Default")
      (node (ref "DD2") (pin "11") (pinfunction "D2/PD2/INT0/PCINT18_11") (pintype "passive"))
    )
    (net (code "68") (name "unconnected-(DD2-D3{slash}PD3{slash}INT1{slash}0C2B{slash}PCINT19-Pad10)") (class "Default")
      (node (ref "DD2") (pin "10") (pinfunction "D3/PD3/INT1/0C2B/PCINT19_10") (pintype "passive"))
    )
    (net (code "69") (name "unconnected-(DD2-D12{slash}PB4{slash}PCINT4{slash}MISO-Pad1)") (class "Default")
      (node (ref "DD2") (pin "1") (pinfunction "D12/PB4/PCINT4/MISO_1") (pintype "passive"))
    )
    (net (code "70") (name "unconnected-(DD2-RST{slash}PC6{slash}~{RESET}{slash}PCINT14-Pad13)") (class "Default")
      (node (ref "DD2") (pin "13") (pinfunction "RST/PC6/~{RESET}/PCINT14_13") (pintype "passive"))
    )
    (net (code "71") (name "unconnected-(DD2-RST{slash}PC6{slash}~{RESET}{slash}PCINT14-Pad18)") (class "Default")
      (node (ref "DD2") (pin "18") (pinfunction "RST/PC6/~{RESET}/PCINT14_18") (pintype "passive"))
    )
    (net (code "72") (name "unconnected-(DD3-NC-Pad3)") (class "Default")
      (node (ref "DD3") (pin "3") (pinfunction "NC_3") (pintype "passive"))
    )
    (net (code "73") (name "unconnected-(DD3-NC-Pad18)") (class "Default")
      (node (ref "DD3") (pin "18") (pinfunction "NC_18") (pintype "passive"))
    )
  )
)
